# KNX-RELAY-8CH_V2.net
KiCad netlist of a schematic drawn in Altium Designer
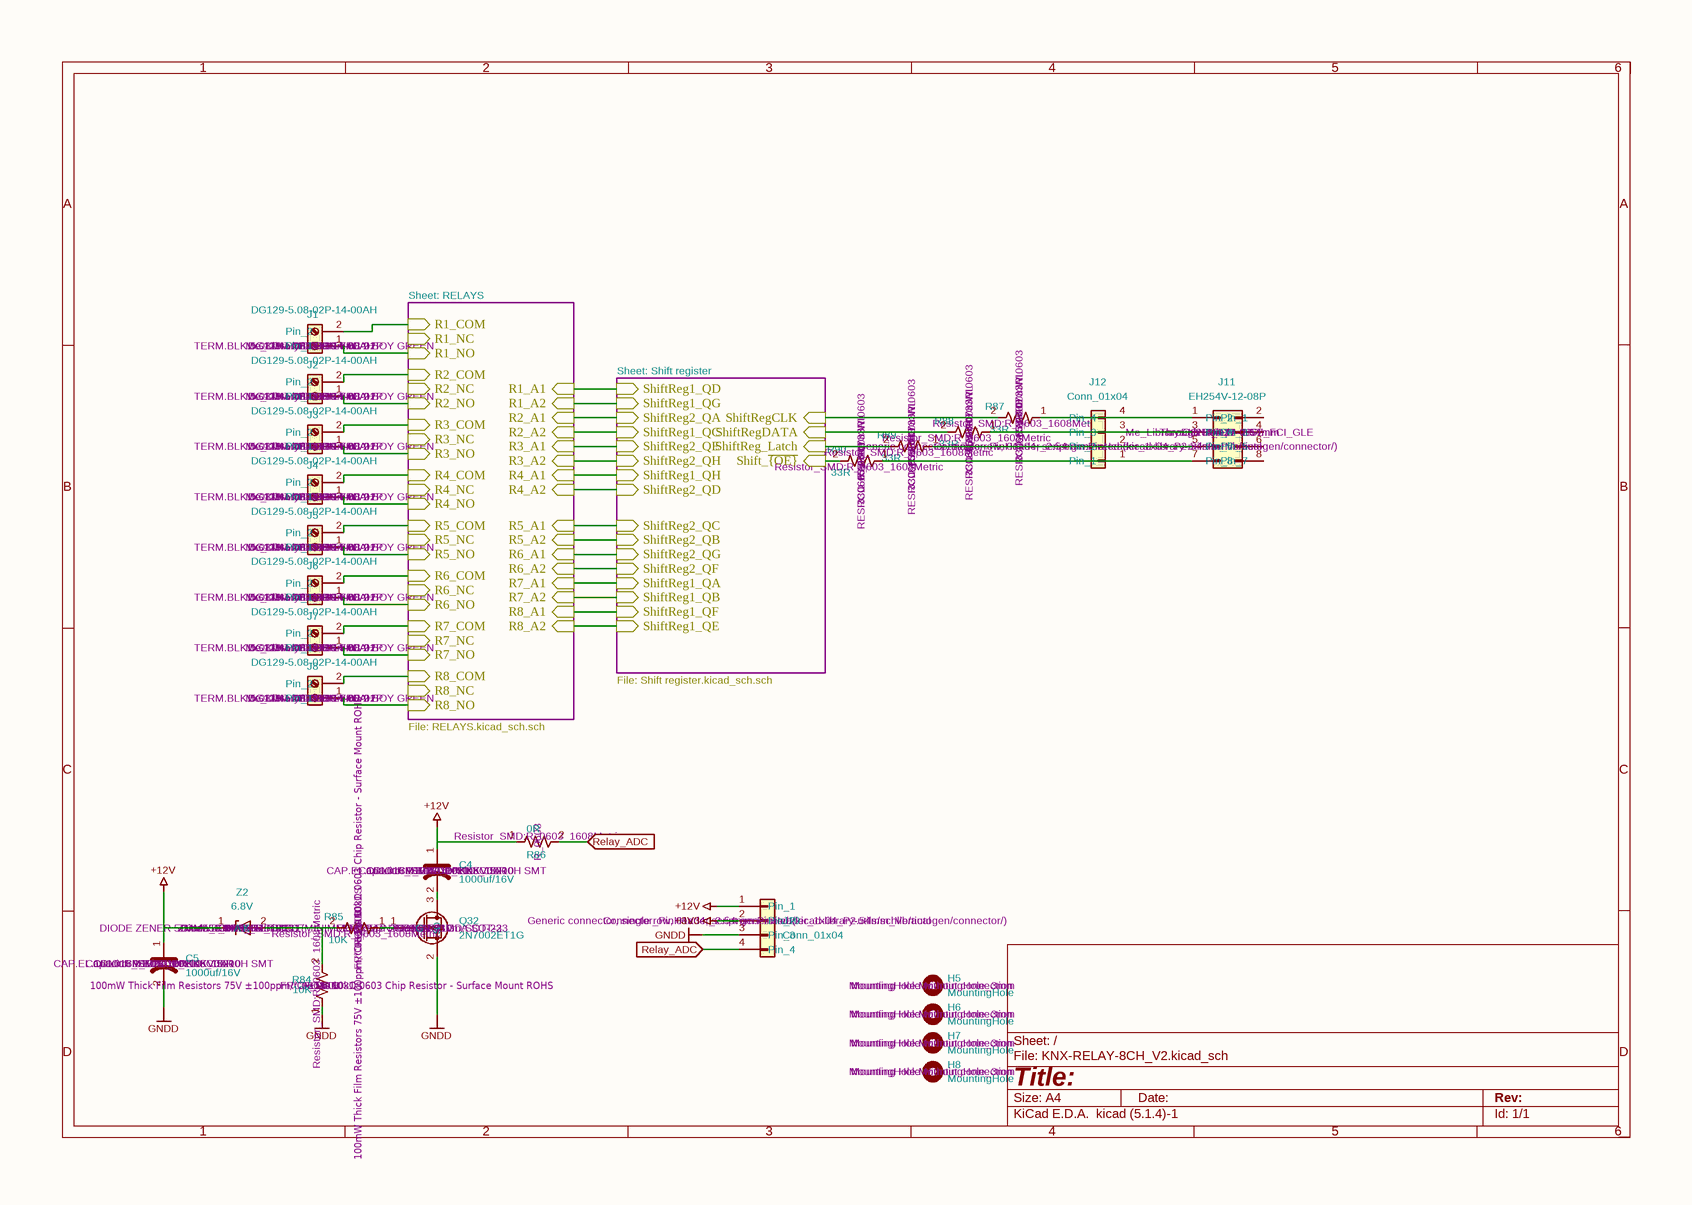
[diagram p0: KNX-RELAY-8CH_V2.SchDoc]

(export (version "E")
  (design (tool "Eeschema 10.0.6"))
  (components
    (comp (ref "C4")
      (value "1000uf/16V")
      (footprint "Capacitor_SMD:CP_Elec_10x10")
      (description "CAP.EL.1000uF 16V 10x10 105C 5000H SMT")
      (fields
        (field (name "MP") "CDL016M102G10PKKKV00R")
        (field (name "MF") " SUSCON")
        (field (name "PACKAGE") "CP_Elec_10x10")
        (field (name "OZD") "CDL016M102G10PKKKV00R")
      )
      (libsource (lib "Device") (part "C_US"))
    )
    (comp (ref "C5")
      (value "1000uf/16V")
      (footprint "Capacitor_SMD:CP_Elec_10x10")
      (description "CAP.EL.1000uF 16V 10x10 105C 5000H SMT")
      (fields
        (field (name "MP") "CDL016M102G10PKKKV00R")
        (field (name "MF") " SUSCON")
        (field (name "PACKAGE") "CP_Elec_10x10")
        (field (name "OZD") "CDL016M102G10PKKKV00R")
      )
      (libsource (lib "Device") (part "C_US"))
    )
    (comp (ref "H5")
      (value "MountingHole")
      (footprint "MountingHole:MountingHole_3mm")
      (description "Mounting Hole without connection")
      (libsource (lib "Mechanical") (part "MountingHole"))
    )
    (comp (ref "H6")
      (value "MountingHole")
      (footprint "MountingHole:MountingHole_3mm")
      (description "Mounting Hole without connection")
      (libsource (lib "Mechanical") (part "MountingHole"))
    )
    (comp (ref "H7")
      (value "MountingHole")
      (footprint "MountingHole:MountingHole_3mm")
      (description "Mounting Hole without connection")
      (libsource (lib "Mechanical") (part "MountingHole"))
    )
    (comp (ref "H8")
      (value "MountingHole")
      (footprint "MountingHole:MountingHole_3mm")
      (description "Mounting Hole without connection")
      (libsource (lib "Mechanical") (part "MountingHole"))
    )
    (comp (ref "J1")
      (value "DG129-5.08-02P-14-00AH")
      (footprint "Me_Library:DG129-5.08-02P")
      (description "TERM.BLK.5.08MM 2P PCB TYPE 2 BOY GREEN")
      (fields
        (field (name "MP") "DG129-5.08-02P-14-00AH")
        (field (name "MF") "DEGSON")
        (field (name "PACKAGE") "THT V/T  5.08mm")
        (field (name "OZD") "DG129-5.08-02P-14-00AH")
      )
      (libsource (lib "Connector") (part "Screw_Terminal_01x02"))
    )
    (comp (ref "J2")
      (value "DG129-5.08-02P-14-00AH")
      (footprint "Me_Library:DG129-5.08-02P")
      (description "TERM.BLK.5.08MM 2P PCB TYPE 2 BOY GREEN")
      (fields
        (field (name "MP") "DG129-5.08-02P-14-00AH")
        (field (name "MF") "DEGSON")
        (field (name "PACKAGE") "THT V/T  5.08mm")
        (field (name "OZD") "DG129-5.08-02P-14-00AH")
      )
      (libsource (lib "Connector") (part "Screw_Terminal_01x02"))
    )
    (comp (ref "J3")
      (value "DG129-5.08-02P-14-00AH")
      (footprint "Me_Library:DG129-5.08-02P")
      (description "TERM.BLK.5.08MM 2P PCB TYPE 2 BOY GREEN")
      (fields
        (field (name "MP") "DG129-5.08-02P-14-00AH")
        (field (name "MF") "DEGSON")
        (field (name "PACKAGE") "THT V/T  5.08mm")
        (field (name "OZD") "DG129-5.08-02P-14-00AH")
      )
      (libsource (lib "Connector") (part "Screw_Terminal_01x02"))
    )
    (comp (ref "J4")
      (value "DG129-5.08-02P-14-00AH")
      (footprint "Me_Library:DG129-5.08-02P")
      (description "TERM.BLK.5.08MM 2P PCB TYPE 2 BOY GREEN")
      (fields
        (field (name "MP") "DG129-5.08-02P-14-00AH")
        (field (name "MF") "DEGSON")
        (field (name "PACKAGE") "THT V/T  5.08mm")
        (field (name "OZD") "DG129-5.08-02P-14-00AH")
      )
      (libsource (lib "Connector") (part "Screw_Terminal_01x02"))
    )
    (comp (ref "J5")
      (value "DG129-5.08-02P-14-00AH")
      (footprint "Me_Library:DG129-5.08-02P")
      (description "TERM.BLK.5.08MM 2P PCB TYPE 2 BOY GREEN")
      (fields
        (field (name "MP") "DG129-5.08-02P-14-00AH")
        (field (name "MF") "DEGSON")
        (field (name "PACKAGE") "THT V/T  5.08mm")
        (field (name "OZD") "DG129-5.08-02P-14-00AH")
      )
      (libsource (lib "Connector") (part "Screw_Terminal_01x02"))
    )
    (comp (ref "J6")
      (value "DG129-5.08-02P-14-00AH")
      (footprint "Me_Library:DG129-5.08-02P")
      (description "TERM.BLK.5.08MM 2P PCB TYPE 2 BOY GREEN")
      (fields
        (field (name "MP") "DG129-5.08-02P-14-00AH")
        (field (name "MF") "DEGSON")
        (field (name "PACKAGE") "THT V/T  5.08mm")
        (field (name "OZD") "DG129-5.08-02P-14-00AH")
      )
      (libsource (lib "Connector") (part "Screw_Terminal_01x02"))
    )
    (comp (ref "J7")
      (value "DG129-5.08-02P-14-00AH")
      (footprint "Me_Library:DG129-5.08-02P")
      (description "TERM.BLK.5.08MM 2P PCB TYPE 2 BOY GREEN")
      (fields
        (field (name "MP") "DG129-5.08-02P-14-00AH")
        (field (name "MF") "DEGSON")
        (field (name "PACKAGE") "THT V/T  5.08mm")
        (field (name "OZD") "DG129-5.08-02P-14-00AH")
      )
      (libsource (lib "Connector") (part "Screw_Terminal_01x02"))
    )
    (comp (ref "J8")
      (value "DG129-5.08-02P-14-00AH")
      (footprint "Me_Library:DG129-5.08-02P")
      (description "TERM.BLK.5.08MM 2P PCB TYPE 2 BOY GREEN")
      (fields
        (field (name "MP") "DG129-5.08-02P-14-00AH")
        (field (name "MF") "DEGSON")
        (field (name "PACKAGE") "THT V/T  5.08mm")
        (field (name "OZD") "DG129-5.08-02P-14-00AH")
      )
      (libsource (lib "Connector") (part "Screw_Terminal_01x02"))
    )
    (comp (ref "J10")
      (value "Conn_01x04")
      (footprint "Connector_PinHeader_2.54mm:PinHeader_1x04_P2.54mm_Vertical")
      (description "Generic connector, single row, 01x04, script generated (kicad-library-utils/schlib/autogen/connector/)")
      (libsource (lib "") (part "Conn_01x04_1"))
    )
    (comp (ref "J11")
      (value "EH254V-12-08P")
      (footprint "Me_Library:CON8_2X4_USZ_FCI_GLE")
      (description "Through Hole,P=2.54mm")
      (fields
        (field (name "MP") "EH254V-12-08P")
        (field (name "MF") "XFCN")
        (field (name "PACKAGE") "Through Hole,P=2.54mm")
      )
      (libsource (lib "Connector_Generic") (part "Conn_02x04_Odd_Even"))
    )
    (comp (ref "J12")
      (value "Conn_01x04")
      (footprint "Connector_PinHeader_2.54mm:PinHeader_1x04_P2.54mm_Vertical")
      (description "Generic connector, single row, 01x04, script generated (kicad-library-utils/schlib/autogen/connector/)")
      (libsource (lib "Connector_Generic") (part "Conn_01x04"))
    )
    (comp (ref "Q32")
      (value "2N7002ET1G")
      (footprint "Package_TO_SOT_SMD:SOT-23")
      (description "MOSFET N-CH 60V 310mA SOT-23")
      (fields
        (field (name "MP") "2N7002ET1G")
        (field (name "MF") "onsemi")
        (field (name "PACKAGE") "SOT-23")
        (field (name "OZD") "2N7002ET1G")
      )
      (libsource (lib "Transistor_FET_Other") (part "Q_NMOS_Depletion_GSD"))
    )
    (comp (ref "R84")
      (value "10K")
      (footprint "Resistor_SMD:R_0603_1608Metric")
      (description "100mW Thick Film Resistors 75V ±100ppm/℃ ±5% 10kΩ 0603 Chip Resistor - Surface Mount ROHS")
      (fields
        (field (name "MP") "FRC0603J103TS")
        (field (name "MF") "FOJAN")
        (field (name "PACKAGE") "R_0603")
      )
      (libsource (lib "Device") (part "R_US"))
    )
    (comp (ref "R85")
      (value "10K")
      (footprint "Resistor_SMD:R_0603_1608Metric")
      (description "100mW Thick Film Resistors 75V ±100ppm/℃ ±5% 10kΩ 0603 Chip Resistor - Surface Mount ROHS")
      (fields
        (field (name "MP") "FRC0603J103TS")
        (field (name "MF") "FOJAN")
        (field (name "PACKAGE") "R_0603")
      )
      (libsource (lib "Device") (part "R_US"))
    )
    (comp (ref "R86")
      (value "0R")
      (footprint "Resistor_SMD:R_0603_1608Metric")
      (fields (field (name "PACKAGE") "R_0603"))
      (libsource (lib "Device") (part "R_US"))
    )
    (comp (ref "R87")
      (value "33R")
      (footprint "Resistor_SMD:R_0603_1608Metric")
      (description "RES 33Ω ±5% 100mW 0603")
      (fields
        (field (name "MP") "RC0603JR-0733RL")
        (field (name "MF") "YAGEO")
        (field (name "PACKAGE") "R_0603")
        (field (name "OZD") "RC0603JR-0733RL")
      )
      (libsource (lib "Device") (part "R_US"))
    )
    (comp (ref "R88")
      (value "33R")
      (footprint "Resistor_SMD:R_0603_1608Metric")
      (description "RES 33Ω ±5% 100mW 0603")
      (fields
        (field (name "MP") "RC0603JR-0733RL")
        (field (name "MF") "YAGEO")
        (field (name "PACKAGE") "R_0603")
        (field (name "OZD") "RC0603JR-0733RL")
      )
      (libsource (lib "Device") (part "R_US"))
    )
    (comp (ref "R89")
      (value "33R")
      (footprint "Resistor_SMD:R_0603_1608Metric")
      (description "RES 33Ω ±5% 100mW 0603")
      (fields
        (field (name "MP") "RC0603JR-0733RL")
        (field (name "MF") "YAGEO")
        (field (name "PACKAGE") "R_0603")
        (field (name "OZD") "RC0603JR-0733RL")
      )
      (libsource (lib "Device") (part "R_US"))
    )
    (comp (ref "R90")
      (value "33R")
      (footprint "Resistor_SMD:R_0603_1608Metric")
      (description "RES 33Ω ±5% 100mW 0603")
      (fields
        (field (name "MP") "RC0603JR-0733RL")
        (field (name "MF") "YAGEO")
        (field (name "PACKAGE") "R_0603")
        (field (name "OZD") "RC0603JR-0733RL")
      )
      (libsource (lib "Device") (part "R_US"))
    )
    (comp (ref "Z2")
      (value "6.8V")
      (footprint "Diode_SMD:D_MiniMELF")
      (description "DIODE ZENER 500mW 6.8V ±5% SOD80 (MINIMELF) SMT")
      (fields
        (field (name "MP") "ZMM55-C6V8_R1_10001")
        (field (name "MF") "PANJIT")
        (field (name "PACKAGE") "D_MiniMELF")
        (field (name "OZD") "ZMM55-C6V8_R1_10001")
      )
      (libsource (lib "Device") (part "D_Zener"))
    )
  )
  (nets
    (net (code "1") (name "+3V3") (class "Default")
      (node (ref "J10") (pin "2") (pinfunction "Pin_2_2") (pintype "passive"))
    )
    (net (code "2") (name "+12V") (class "Default")
      (node (ref "C4") (pin "1") (pinfunction "1_1") (pintype "passive"))
      (node (ref "C5") (pin "1") (pinfunction "1_1") (pintype "passive"))
      (node (ref "J10") (pin "1") (pinfunction "Pin_1_1") (pintype "passive"))
      (node (ref "R86") (pin "1") (pinfunction "1_1") (pintype "passive"))
      (node (ref "Z2") (pin "1") (pinfunction "K_1") (pintype "passive"))
    )
    (net (code "5") (name "/R1_COM") (class "Default")
      (node (ref "J1") (pin "2") (pinfunction "Pin_2_2") (pintype "passive"))
    )
    (net (code "7") (name "/R1_NO") (class "Default")
      (node (ref "J1") (pin "1") (pinfunction "Pin_1_1") (pintype "passive"))
    )
    (net (code "10") (name "/R2_COM") (class "Default")
      (node (ref "J2") (pin "2") (pinfunction "Pin_2_2") (pintype "passive"))
    )
    (net (code "12") (name "/R2_NO") (class "Default")
      (node (ref "J2") (pin "1") (pinfunction "Pin_1_1") (pintype "passive"))
    )
    (net (code "15") (name "/R3_COM") (class "Default")
      (node (ref "J3") (pin "2") (pinfunction "Pin_2_2") (pintype "passive"))
    )
    (net (code "17") (name "/R3_NO") (class "Default")
      (node (ref "J3") (pin "1") (pinfunction "Pin_1_1") (pintype "passive"))
    )
    (net (code "20") (name "/R4_COM") (class "Default")
      (node (ref "J4") (pin "2") (pinfunction "Pin_2_2") (pintype "passive"))
    )
    (net (code "22") (name "/R4_NO") (class "Default")
      (node (ref "J4") (pin "1") (pinfunction "Pin_1_1") (pintype "passive"))
    )
    (net (code "25") (name "/R5_COM") (class "Default")
      (node (ref "J5") (pin "2") (pinfunction "Pin_2_2") (pintype "passive"))
    )
    (net (code "27") (name "/R5_NO") (class "Default")
      (node (ref "J5") (pin "1") (pinfunction "Pin_1_1") (pintype "passive"))
    )
    (net (code "30") (name "/R6_COM") (class "Default")
      (node (ref "J6") (pin "2") (pinfunction "Pin_2_2") (pintype "passive"))
    )
    (net (code "32") (name "/R6_NO") (class "Default")
      (node (ref "J6") (pin "1") (pinfunction "Pin_1_1") (pintype "passive"))
    )
    (net (code "35") (name "/R7_COM") (class "Default")
      (node (ref "J7") (pin "2") (pinfunction "Pin_2_2") (pintype "passive"))
    )
    (net (code "37") (name "/R7_NO") (class "Default")
      (node (ref "J7") (pin "1") (pinfunction "Pin_1_1") (pintype "passive"))
    )
    (net (code "40") (name "/R8_COM") (class "Default")
      (node (ref "J8") (pin "2") (pinfunction "Pin_2_2") (pintype "passive"))
    )
    (net (code "42") (name "/R8_NO") (class "Default")
      (node (ref "J8") (pin "1") (pinfunction "Pin_1_1") (pintype "passive"))
    )
    (net (code "43") (name "/Relay_ADC") (class "Default")
      (node (ref "J10") (pin "4") (pinfunction "Pin_4_4") (pintype "passive"))
      (node (ref "R86") (pin "2") (pinfunction "2_2") (pintype "passive"))
    )
    (net (code "44") (name "/ShiftRegCLK") (class "Default")
      (node (ref "R87") (pin "2") (pinfunction "2_2") (pintype "passive"))
    )
    (net (code "45") (name "/ShiftRegDATA") (class "Default")
      (node (ref "R88") (pin "2") (pinfunction "2_2") (pintype "passive"))
    )
    (net (code "46") (name "/ShiftReg_Latch") (class "Default")
      (node (ref "R89") (pin "2") (pinfunction "2_2") (pintype "passive"))
    )
    (net (code "47") (name "/Shift_~{{OE}}") (class "Default")
      (node (ref "R90") (pin "2") (pinfunction "2_2") (pintype "passive"))
    )
    (net (code "48") (name "GNDD") (class "Default")
      (node (ref "C5") (pin "2") (pinfunction "2_2") (pintype "passive"))
      (node (ref "J10") (pin "3") (pinfunction "Pin_3_3") (pintype "passive"))
      (node (ref "Q32") (pin "2") (pinfunction "S_2") (pintype "passive"))
      (node (ref "R84") (pin "1") (pinfunction "1_1") (pintype "passive"))
    )
    (net (code "49") (name "Net-(J11-Pin_1)") (class "Default")
      (node (ref "J11") (pin "1") (pinfunction "Pin_1_1") (pintype "passive"))
      (node (ref "J12") (pin "4") (pinfunction "Pin_4_4") (pintype "passive"))
      (node (ref "R87") (pin "1") (pinfunction "1_1") (pintype "passive"))
    )
    (net (code "50") (name "Net-(J11-Pin_3)") (class "Default")
      (node (ref "J11") (pin "3") (pinfunction "Pin_3_3") (pintype "passive"))
      (node (ref "J12") (pin "3") (pinfunction "Pin_3_3") (pintype "passive"))
      (node (ref "R88") (pin "1") (pinfunction "1_1") (pintype "passive"))
    )
    (net (code "51") (name "Net-(J11-Pin_5)") (class "Default")
      (node (ref "J11") (pin "5") (pinfunction "Pin_5_5") (pintype "passive"))
      (node (ref "J12") (pin "2") (pinfunction "Pin_2_2") (pintype "passive"))
      (node (ref "R89") (pin "1") (pinfunction "1_1") (pintype "passive"))
    )
    (net (code "52") (name "Net-(J11-Pin_7)") (class "Default")
      (node (ref "J11") (pin "7") (pinfunction "Pin_7_7") (pintype "passive"))
      (node (ref "J12") (pin "1") (pinfunction "Pin_1_1") (pintype "passive"))
      (node (ref "R90") (pin "1") (pinfunction "1_1") (pintype "passive"))
    )
    (net (code "53") (name "Net-(Q32-D)") (class "Default")
      (node (ref "C4") (pin "2") (pinfunction "2_2") (pintype "passive"))
      (node (ref "Q32") (pin "3") (pinfunction "D_3") (pintype "passive"))
    )
    (net (code "54") (name "Net-(Q32-G)") (class "Default")
      (node (ref "Q32") (pin "1") (pinfunction "G_1") (pintype "passive"))
      (node (ref "R85") (pin "1") (pinfunction "1_1") (pintype "passive"))
    )
    (net (code "55") (name "Net-(Z2-A)") (class "Default")
      (node (ref "R84") (pin "2") (pinfunction "2_2") (pintype "passive"))
      (node (ref "R85") (pin "2") (pinfunction "2_2") (pintype "passive"))
      (node (ref "Z2") (pin "2") (pinfunction "A_2") (pintype "passive"))
    )
    (net (code "56") (name "unconnected-(J11-Pin_2-Pad2)") (class "Default")
      (node (ref "J11") (pin "2") (pinfunction "Pin_2_2") (pintype "passive"))
    )
    (net (code "57") (name "unconnected-(J11-Pin_4-Pad4)") (class "Default")
      (node (ref "J11") (pin "4") (pinfunction "Pin_4_4") (pintype "passive"))
    )
    (net (code "58") (name "unconnected-(J11-Pin_6-Pad6)") (class "Default")
      (node (ref "J11") (pin "6") (pinfunction "Pin_6_6") (pintype "passive"))
    )
    (net (code "59") (name "unconnected-(J11-Pin_8-Pad8)") (class "Default")
      (node (ref "J11") (pin "8") (pinfunction "Pin_8_8") (pintype "passive"))
    )
  )
)
